# Connectors.net
KiCad netlist of a schematic drawn in Altium Designer
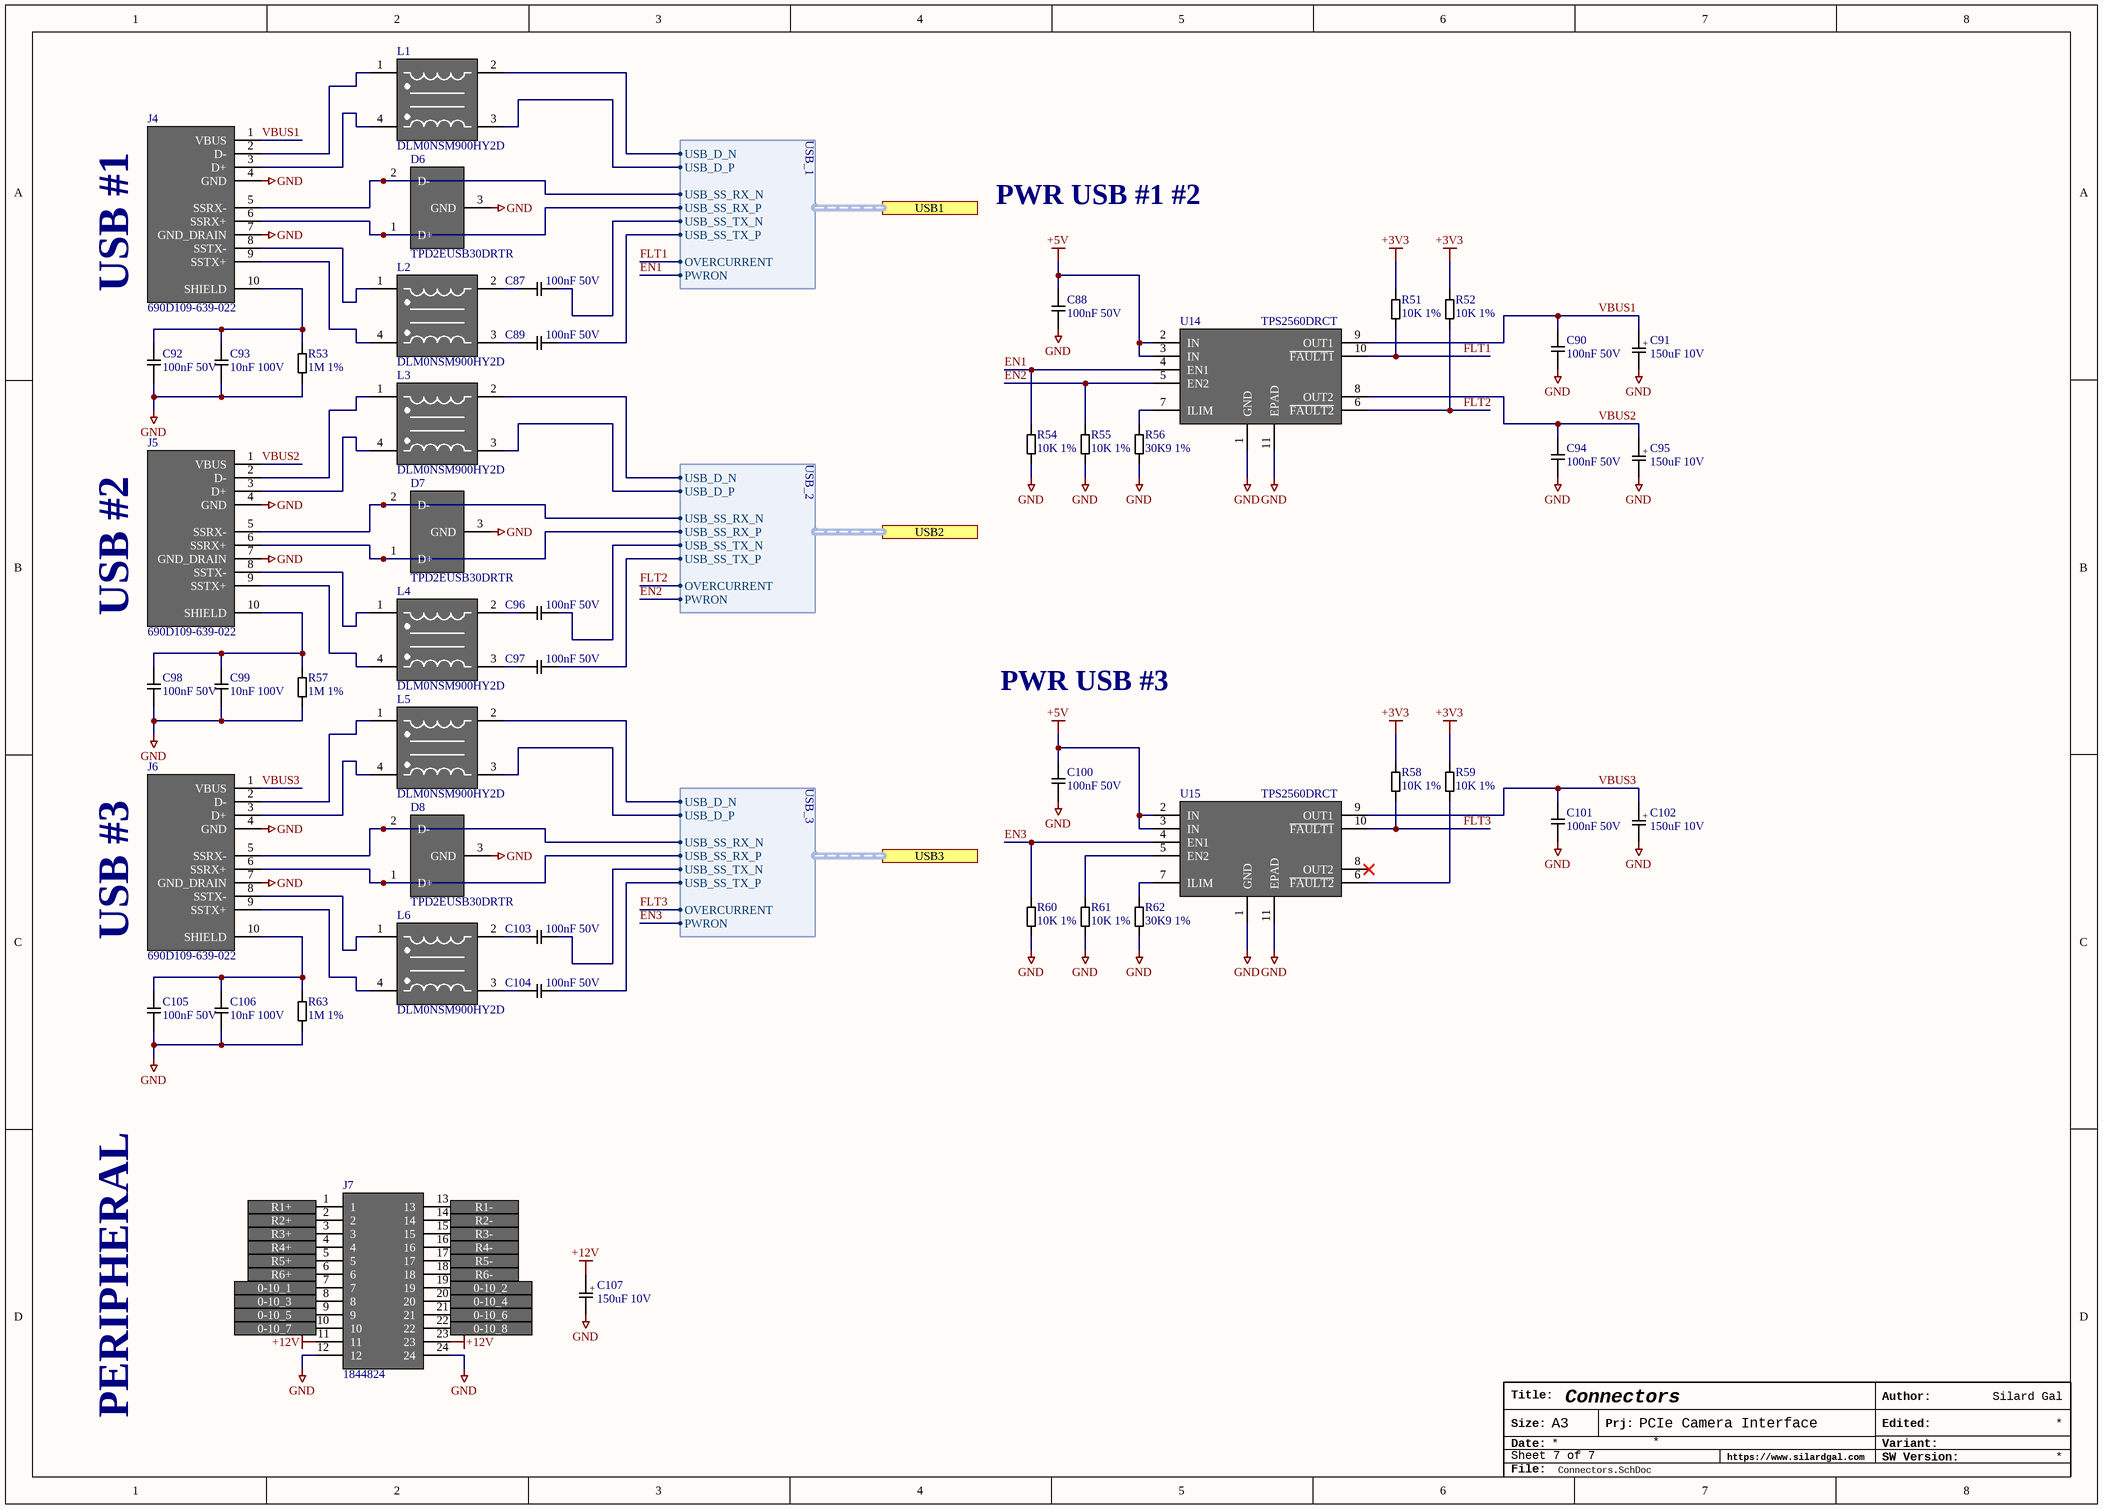
[diagram p0: Connectors.SchDoc]

(export (version "E")
  (design (tool "Eeschema 10.0.6"))
  (components
    (comp (ref "C87")
      (value "100nF 50V")
      (footprint "CAPC1005X06N")
      (description "0.1 µF ±10% 16V Ceramic Capacitor X7R 0402 (1005 Metric)")
      (fields (field (name "MPN") "GRM155R71C104KA88J"))
      (libsource (lib "PCIe_Camera_Interface_Library") (part "100nF 50V_1"))
    )
    (comp (ref "C88")
      (value "100nF 50V")
      (footprint "CAPC1608X06N")
      (description "0.1 µF ±10% 50V Ceramic Capacitor X7R 0603 (1608 Metric)")
      (fields (field (name "MPN") "GCM188R71H104KA57D"))
      (libsource (lib "PCIe_Camera_Interface_Library") (part "100nF 50V"))
    )
    (comp (ref "C89")
      (value "100nF 50V")
      (footprint "CAPC1005X06N")
      (description "0.1 µF ±10% 16V Ceramic Capacitor X7R 0402 (1005 Metric)")
      (fields (field (name "MPN") "GRM155R71C104KA88J"))
      (libsource (lib "PCIe_Camera_Interface_Library") (part "100nF 50V_1"))
    )
    (comp (ref "C90")
      (value "100nF 50V")
      (footprint "CAPC1608X06N")
      (description "0.1 µF ±10% 50V Ceramic Capacitor X7R 0603 (1608 Metric)")
      (fields (field (name "MPN") "GCM188R71H104KA57D"))
      (libsource (lib "PCIe_Camera_Interface_Library") (part "100nF 50V"))
    )
    (comp (ref "C91")
      (value "150uF 10V")
      (footprint "CAP66x66x58")
      (description "150 µF 10 V Aluminum - Polymer Capacitors Radial, Can - SMD 30mOhm 2000 Hrs @ 105°C")
      (fields (field (name "MPN") "875105244011"))
      (libsource (lib "PCIe_Camera_Interface_Library") (part "150uF 10V"))
    )
    (comp (ref "C92")
      (value "100nF 50V")
      (footprint "CAPC1608X06N")
      (description "0.1 µF ±10% 50V Ceramic Capacitor X7R 0603 (1608 Metric)")
      (fields (field (name "MPN") "GCM188R71H104KA57D"))
      (libsource (lib "PCIe_Camera_Interface_Library") (part "100nF 50V"))
    )
    (comp (ref "C93")
      (value "10nF 100V")
      (footprint "CAPC1608X06N")
      (description "10000 pF ±10% 100V Ceramic Capacitor X7R 0603 (1608 Metric)")
      (fields (field (name "MPN") "GCM188R72A103KA37D"))
      (libsource (lib "PCIe_Camera_Interface_Library") (part "10nF 100V"))
    )
    (comp (ref "C94")
      (value "100nF 50V")
      (footprint "CAPC1608X06N")
      (description "0.1 µF ±10% 50V Ceramic Capacitor X7R 0603 (1608 Metric)")
      (fields (field (name "MPN") "GCM188R71H104KA57D"))
      (libsource (lib "PCIe_Camera_Interface_Library") (part "100nF 50V"))
    )
    (comp (ref "C95")
      (value "150uF 10V")
      (footprint "CAP66x66x58")
      (description "150 µF 10 V Aluminum - Polymer Capacitors Radial, Can - SMD 30mOhm 2000 Hrs @ 105°C")
      (fields (field (name "MPN") "875105244011"))
      (libsource (lib "PCIe_Camera_Interface_Library") (part "150uF 10V"))
    )
    (comp (ref "C96")
      (value "100nF 50V")
      (footprint "CAPC1005X06N")
      (description "0.1 µF ±10% 16V Ceramic Capacitor X7R 0402 (1005 Metric)")
      (fields (field (name "MPN") "GRM155R71C104KA88J"))
      (libsource (lib "PCIe_Camera_Interface_Library") (part "100nF 50V_1"))
    )
    (comp (ref "C97")
      (value "100nF 50V")
      (footprint "CAPC1005X06N")
      (description "0.1 µF ±10% 16V Ceramic Capacitor X7R 0402 (1005 Metric)")
      (fields (field (name "MPN") "GRM155R71C104KA88J"))
      (libsource (lib "PCIe_Camera_Interface_Library") (part "100nF 50V_1"))
    )
    (comp (ref "C98")
      (value "100nF 50V")
      (footprint "CAPC1608X06N")
      (description "0.1 µF ±10% 50V Ceramic Capacitor X7R 0603 (1608 Metric)")
      (fields (field (name "MPN") "GCM188R71H104KA57D"))
      (libsource (lib "PCIe_Camera_Interface_Library") (part "100nF 50V"))
    )
    (comp (ref "C99")
      (value "10nF 100V")
      (footprint "CAPC1608X06N")
      (description "10000 pF ±10% 100V Ceramic Capacitor X7R 0603 (1608 Metric)")
      (fields (field (name "MPN") "GCM188R72A103KA37D"))
      (libsource (lib "PCIe_Camera_Interface_Library") (part "10nF 100V"))
    )
    (comp (ref "C100")
      (value "100nF 50V")
      (footprint "CAPC1608X06N")
      (description "0.1 µF ±10% 50V Ceramic Capacitor X7R 0603 (1608 Metric)")
      (fields (field (name "MPN") "GCM188R71H104KA57D"))
      (libsource (lib "PCIe_Camera_Interface_Library") (part "100nF 50V"))
    )
    (comp (ref "C101")
      (value "100nF 50V")
      (footprint "CAPC1608X06N")
      (description "0.1 µF ±10% 50V Ceramic Capacitor X7R 0603 (1608 Metric)")
      (fields (field (name "MPN") "GCM188R71H104KA57D"))
      (libsource (lib "PCIe_Camera_Interface_Library") (part "100nF 50V"))
    )
    (comp (ref "C102")
      (value "150uF 10V")
      (footprint "CAP66x66x58")
      (description "150 µF 10 V Aluminum - Polymer Capacitors Radial, Can - SMD 30mOhm 2000 Hrs @ 105°C")
      (fields (field (name "MPN") "875105244011"))
      (libsource (lib "PCIe_Camera_Interface_Library") (part "150uF 10V"))
    )
    (comp (ref "C103")
      (value "100nF 50V")
      (footprint "CAPC1005X06N")
      (description "0.1 µF ±10% 16V Ceramic Capacitor X7R 0402 (1005 Metric)")
      (fields (field (name "MPN") "GRM155R71C104KA88J"))
      (libsource (lib "PCIe_Camera_Interface_Library") (part "100nF 50V_1"))
    )
    (comp (ref "C104")
      (value "100nF 50V")
      (footprint "CAPC1005X06N")
      (description "0.1 µF ±10% 16V Ceramic Capacitor X7R 0402 (1005 Metric)")
      (fields (field (name "MPN") "GRM155R71C104KA88J"))
      (libsource (lib "PCIe_Camera_Interface_Library") (part "100nF 50V_1"))
    )
    (comp (ref "C105")
      (value "100nF 50V")
      (footprint "CAPC1608X06N")
      (description "0.1 µF ±10% 50V Ceramic Capacitor X7R 0603 (1608 Metric)")
      (fields (field (name "MPN") "GCM188R71H104KA57D"))
      (libsource (lib "PCIe_Camera_Interface_Library") (part "100nF 50V"))
    )
    (comp (ref "C106")
      (value "10nF 100V")
      (footprint "CAPC1608X06N")
      (description "10000 pF ±10% 100V Ceramic Capacitor X7R 0603 (1608 Metric)")
      (fields (field (name "MPN") "GCM188R72A103KA37D"))
      (libsource (lib "PCIe_Camera_Interface_Library") (part "10nF 100V"))
    )
    (comp (ref "C107")
      (value "150uF 10V")
      (footprint "CAP66x66x58")
      (description "150 µF 10 V Aluminum - Polymer Capacitors Radial, Can - SMD 30mOhm 2000 Hrs @ 105°C")
      (fields (field (name "MPN") "875105244011"))
      (libsource (lib "PCIe_Camera_Interface_Library") (part "150uF 10V"))
    )
    (comp (ref "D6")
      (value "TPD2EUSB30DRTR")
      (footprint "SOTFL35P100X50-3N")
      (description "8V Clamp 5A (8/20µs) Ipp Tvs Diode Surface Mount SOT-3")
      (libsource (lib "PCIe_Camera_Interface_Library") (part "TPD2EUSB30DRTR"))
    )
    (comp (ref "D7")
      (value "TPD2EUSB30DRTR")
      (footprint "SOTFL35P100X50-3N")
      (description "8V Clamp 5A (8/20µs) Ipp Tvs Diode Surface Mount SOT-3")
      (libsource (lib "PCIe_Camera_Interface_Library") (part "TPD2EUSB30DRTR"))
    )
    (comp (ref "D8")
      (value "TPD2EUSB30DRTR")
      (footprint "SOTFL35P100X50-3N")
      (description "8V Clamp 5A (8/20µs) Ipp Tvs Diode Surface Mount SOT-3")
      (libsource (lib "PCIe_Camera_Interface_Library") (part "TPD2EUSB30DRTR"))
    )
    (comp (ref "J4")
      (value "690D109-639-022")
      (footprint "690D109-639-022")
      (description "USB-A (USB TYPE-A) USB 3.0 Receptacle Connector 9 Position Through Hole, Right Angle")
      (libsource (lib "PCIe_Camera_Interface_Library") (part "690D109-639-022"))
    )
    (comp (ref "J5")
      (value "690D109-639-022")
      (footprint "690D109-639-022")
      (description "USB-A (USB TYPE-A) USB 3.0 Receptacle Connector 9 Position Through Hole, Right Angle")
      (libsource (lib "PCIe_Camera_Interface_Library") (part "690D109-639-022"))
    )
    (comp (ref "J6")
      (value "690D109-639-022")
      (footprint "690D109-639-022")
      (description "USB-A (USB TYPE-A) USB 3.0 Receptacle Connector 9 Position Through Hole, Right Angle")
      (libsource (lib "PCIe_Camera_Interface_Library") (part "690D109-639-022"))
    )
    (comp (ref "J7")
      (value "1844824")
      (footprint "PHOENIX_1844824")
      (libsource (lib "PCIe_Camera_Interface_Library") (part "1844824"))
    )
    (comp (ref "L1")
      (value "DLM0NSM900HY2D")
      (footprint "DLM0NSM900HY2D")
      (description "2 Line Common Mode Choke Surface Mount 90 Ohms @ 100 MHz 100mA DCR 4Ohm")
      (libsource (lib "PCIe_Camera_Interface_Library") (part "DLM0NSM900HY2D"))
    )
    (comp (ref "L2")
      (value "DLM0NSM900HY2D")
      (footprint "DLM0NSM900HY2D")
      (description "2 Line Common Mode Choke Surface Mount 90 Ohms @ 100 MHz 100mA DCR 4Ohm")
      (libsource (lib "PCIe_Camera_Interface_Library") (part "DLM0NSM900HY2D"))
    )
    (comp (ref "L3")
      (value "DLM0NSM900HY2D")
      (footprint "DLM0NSM900HY2D")
      (description "2 Line Common Mode Choke Surface Mount 90 Ohms @ 100 MHz 100mA DCR 4Ohm")
      (libsource (lib "PCIe_Camera_Interface_Library") (part "DLM0NSM900HY2D"))
    )
    (comp (ref "L4")
      (value "DLM0NSM900HY2D")
      (footprint "DLM0NSM900HY2D")
      (description "2 Line Common Mode Choke Surface Mount 90 Ohms @ 100 MHz 100mA DCR 4Ohm")
      (libsource (lib "PCIe_Camera_Interface_Library") (part "DLM0NSM900HY2D"))
    )
    (comp (ref "L5")
      (value "DLM0NSM900HY2D")
      (footprint "DLM0NSM900HY2D")
      (description "2 Line Common Mode Choke Surface Mount 90 Ohms @ 100 MHz 100mA DCR 4Ohm")
      (libsource (lib "PCIe_Camera_Interface_Library") (part "DLM0NSM900HY2D"))
    )
    (comp (ref "L6")
      (value "DLM0NSM900HY2D")
      (footprint "DLM0NSM900HY2D")
      (description "2 Line Common Mode Choke Surface Mount 90 Ohms @ 100 MHz 100mA DCR 4Ohm")
      (libsource (lib "PCIe_Camera_Interface_Library") (part "DLM0NSM900HY2D"))
    )
    (comp (ref "R51")
      (value "10K 1%")
      (footprint "RESC1608X06N")
      (description "10 kOhms ±1% 0.1W, 1/10W Chip Resistor 0603 (1608 Metric) Automotive AEC-Q200 Thick Film")
      (fields (field (name "MPN") "ERJ-3EKF1002V"))
      (libsource (lib "PCIe_Camera_Interface_Library") (part "10K 1%"))
    )
    (comp (ref "R52")
      (value "10K 1%")
      (footprint "RESC1608X06N")
      (description "10 kOhms ±1% 0.1W, 1/10W Chip Resistor 0603 (1608 Metric) Automotive AEC-Q200 Thick Film")
      (fields (field (name "MPN") "ERJ-3EKF1002V"))
      (libsource (lib "PCIe_Camera_Interface_Library") (part "10K 1%"))
    )
    (comp (ref "R53")
      (value "1M 1%")
      (footprint "RESC1608X06N")
      (description "RES SMD 1M OHM 1% 1/10W 0603")
      (fields (field (name "MPN") "ERJ-3EKF1004V"))
      (libsource (lib "PCIe_Camera_Interface_Library") (part "1M 1%"))
    )
    (comp (ref "R54")
      (value "10K 1%")
      (footprint "RESC1608X06N")
      (description "10 kOhms ±1% 0.1W, 1/10W Chip Resistor 0603 (1608 Metric) Automotive AEC-Q200 Thick Film")
      (fields (field (name "MPN") "ERJ-3EKF1002V"))
      (libsource (lib "PCIe_Camera_Interface_Library") (part "10K 1%"))
    )
    (comp (ref "R55")
      (value "10K 1%")
      (footprint "RESC1608X06N")
      (description "10 kOhms ±1% 0.1W, 1/10W Chip Resistor 0603 (1608 Metric) Automotive AEC-Q200 Thick Film")
      (fields (field (name "MPN") "ERJ-3EKF1002V"))
      (libsource (lib "PCIe_Camera_Interface_Library") (part "10K 1%"))
    )
    (comp (ref "R56")
      (value "30K9 1%")
      (footprint "RESC1608X06N")
      (description "30.9 kOhms ±1% 0.1W, 1/10W Chip Resistor 0603 (1608 Metric) Automotive AEC-Q200 Thick Film")
      (fields (field (name "MPN") "ERJ-3EKF3092V"))
      (libsource (lib "PCIe_Camera_Interface_Library") (part "30K9 1%"))
    )
    (comp (ref "R57")
      (value "1M 1%")
      (footprint "RESC1608X06N")
      (description "RES SMD 1M OHM 1% 1/10W 0603")
      (fields (field (name "MPN") "ERJ-3EKF1004V"))
      (libsource (lib "PCIe_Camera_Interface_Library") (part "1M 1%"))
    )
    (comp (ref "R58")
      (value "10K 1%")
      (footprint "RESC1608X06N")
      (description "10 kOhms ±1% 0.1W, 1/10W Chip Resistor 0603 (1608 Metric) Automotive AEC-Q200 Thick Film")
      (fields (field (name "MPN") "ERJ-3EKF1002V"))
      (libsource (lib "PCIe_Camera_Interface_Library") (part "10K 1%"))
    )
    (comp (ref "R59")
      (value "10K 1%")
      (footprint "RESC1608X06N")
      (description "10 kOhms ±1% 0.1W, 1/10W Chip Resistor 0603 (1608 Metric) Automotive AEC-Q200 Thick Film")
      (fields (field (name "MPN") "ERJ-3EKF1002V"))
      (libsource (lib "PCIe_Camera_Interface_Library") (part "10K 1%"))
    )
    (comp (ref "R60")
      (value "10K 1%")
      (footprint "RESC1608X06N")
      (description "10 kOhms ±1% 0.1W, 1/10W Chip Resistor 0603 (1608 Metric) Automotive AEC-Q200 Thick Film")
      (fields (field (name "MPN") "ERJ-3EKF1002V"))
      (libsource (lib "PCIe_Camera_Interface_Library") (part "10K 1%"))
    )
    (comp (ref "R61")
      (value "10K 1%")
      (footprint "RESC1608X06N")
      (description "10 kOhms ±1% 0.1W, 1/10W Chip Resistor 0603 (1608 Metric) Automotive AEC-Q200 Thick Film")
      (fields (field (name "MPN") "ERJ-3EKF1002V"))
      (libsource (lib "PCIe_Camera_Interface_Library") (part "10K 1%"))
    )
    (comp (ref "R62")
      (value "30K9 1%")
      (footprint "RESC1608X06N")
      (description "30.9 kOhms ±1% 0.1W, 1/10W Chip Resistor 0603 (1608 Metric) Automotive AEC-Q200 Thick Film")
      (fields (field (name "MPN") "ERJ-3EKF3092V"))
      (libsource (lib "PCIe_Camera_Interface_Library") (part "30K9 1%"))
    )
    (comp (ref "R63")
      (value "1M 1%")
      (footprint "RESC1608X06N")
      (description "RES SMD 1M OHM 1% 1/10W 0603")
      (fields (field (name "MPN") "ERJ-3EKF1004V"))
      (libsource (lib "PCIe_Camera_Interface_Library") (part "1M 1%"))
    )
    (comp (ref "U14")
      (value "TPS2560DRCT")
      (footprint "10VSON")
      (description "Power Switch/Driver 1:2 N-Channel 2.5A 10-VSON (3x3)")
      (libsource (lib "PCIe_Camera_Interface_Library") (part "TPS2560DRCT"))
    )
    (comp (ref "U15")
      (value "TPS2560DRCT")
      (footprint "10VSON")
      (description "Power Switch/Driver 1:2 N-Channel 2.5A 10-VSON (3x3)")
      (libsource (lib "PCIe_Camera_Interface_Library") (part "TPS2560DRCT"))
    )
  )
  (nets
    (net (code "4") (name "+3V3") (class "Default")
      (node (ref "R51") (pin "2") (pinfunction "2_2") (pintype "passive"))
      (node (ref "R52") (pin "2") (pinfunction "2_2") (pintype "passive"))
      (node (ref "R58") (pin "2") (pinfunction "2_2") (pintype "passive"))
      (node (ref "R59") (pin "2") (pinfunction "2_2") (pintype "passive"))
    )
    (net (code "5") (name "+5V") (class "Default")
      (node (ref "C100") (pin "2") (pinfunction "2_2") (pintype "passive"))
      (node (ref "C88") (pin "2") (pinfunction "2_2") (pintype "passive"))
      (node (ref "U14") (pin "2") (pinfunction "IN_2") (pintype "passive"))
      (node (ref "U14") (pin "3") (pinfunction "IN_3") (pintype "passive"))
      (node (ref "U15") (pin "2") (pinfunction "IN_2") (pintype "passive"))
      (node (ref "U15") (pin "3") (pinfunction "IN_3") (pintype "passive"))
    )
    (net (code "6") (name "+12V") (class "Default")
      (node (ref "C107") (pin "1") (pinfunction "1_1") (pintype "passive"))
      (node (ref "J7") (pin "11") (pinfunction "11_11") (pintype "passive"))
      (node (ref "J7") (pin "23") (pinfunction "23_23") (pintype "passive"))
    )
    (net (code "7") (name "/0-10_1") (class "Default")
      (node (ref "J7") (pin "7") (pinfunction "7_7") (pintype "passive"))
    )
    (net (code "8") (name "/0-10_2") (class "Default")
      (node (ref "J7") (pin "19") (pinfunction "19_19") (pintype "passive"))
    )
    (net (code "9") (name "/0-10_3") (class "Default")
      (node (ref "J7") (pin "8") (pinfunction "8_8") (pintype "passive"))
    )
    (net (code "10") (name "/0-10_4") (class "Default")
      (node (ref "J7") (pin "20") (pinfunction "20_20") (pintype "passive"))
    )
    (net (code "11") (name "/0-10_5") (class "Default")
      (node (ref "J7") (pin "9") (pinfunction "9_9") (pintype "passive"))
    )
    (net (code "12") (name "/0-10_6") (class "Default")
      (node (ref "J7") (pin "21") (pinfunction "21_21") (pintype "passive"))
    )
    (net (code "13") (name "/0-10_7") (class "Default")
      (node (ref "J7") (pin "10") (pinfunction "10_10") (pintype "passive"))
    )
    (net (code "14") (name "/0-10_8") (class "Default")
      (node (ref "J7") (pin "22") (pinfunction "22_22") (pintype "passive"))
    )
    (net (code "15") (name "/EN1") (class "Default")
      (node (ref "R54") (pin "2") (pinfunction "2_2") (pintype "passive"))
      (node (ref "U14") (pin "4") (pinfunction "EN1_4") (pintype "passive"))
    )
    (net (code "16") (name "/EN2") (class "Default")
      (node (ref "R55") (pin "2") (pinfunction "2_2") (pintype "passive"))
      (node (ref "U14") (pin "5") (pinfunction "EN2_5") (pintype "passive"))
    )
    (net (code "17") (name "/EN3") (class "Default")
      (node (ref "R60") (pin "2") (pinfunction "2_2") (pintype "passive"))
      (node (ref "U15") (pin "4") (pinfunction "EN1_4") (pintype "passive"))
    )
    (net (code "18") (name "/FLT1") (class "Default")
      (node (ref "R51") (pin "1") (pinfunction "1_1") (pintype "passive"))
      (node (ref "U14") (pin "10") (pinfunction "~{FAULT1}_10") (pintype "passive"))
    )
    (net (code "19") (name "/FLT2") (class "Default")
      (node (ref "R52") (pin "1") (pinfunction "1_1") (pintype "passive"))
      (node (ref "U14") (pin "6") (pinfunction "~{FAULT2}_6") (pintype "passive"))
    )
    (net (code "20") (name "/FLT3") (class "Default")
      (node (ref "R58") (pin "1") (pinfunction "1_1") (pintype "passive"))
      (node (ref "U15") (pin "10") (pinfunction "~{FAULT1}_10") (pintype "passive"))
    )
    (net (code "21") (name "/R1+") (class "Default")
      (node (ref "J7") (pin "1") (pinfunction "1_1") (pintype "passive"))
    )
    (net (code "22") (name "/R1-") (class "Default")
      (node (ref "J7") (pin "13") (pinfunction "13_13") (pintype "passive"))
    )
    (net (code "23") (name "/R2+") (class "Default")
      (node (ref "J7") (pin "2") (pinfunction "2_2") (pintype "passive"))
    )
    (net (code "24") (name "/R2-") (class "Default")
      (node (ref "J7") (pin "14") (pinfunction "14_14") (pintype "passive"))
    )
    (net (code "25") (name "/R3+") (class "Default")
      (node (ref "J7") (pin "3") (pinfunction "3_3") (pintype "passive"))
    )
    (net (code "26") (name "/R3-") (class "Default")
      (node (ref "J7") (pin "15") (pinfunction "15_15") (pintype "passive"))
    )
    (net (code "27") (name "/R4+") (class "Default")
      (node (ref "J7") (pin "4") (pinfunction "4_4") (pintype "passive"))
    )
    (net (code "28") (name "/R4-") (class "Default")
      (node (ref "J7") (pin "16") (pinfunction "16_16") (pintype "passive"))
    )
    (net (code "29") (name "/R5+") (class "Default")
      (node (ref "J7") (pin "5") (pinfunction "5_5") (pintype "passive"))
    )
    (net (code "30") (name "/R5-") (class "Default")
      (node (ref "J7") (pin "17") (pinfunction "17_17") (pintype "passive"))
    )
    (net (code "31") (name "/R6+") (class "Default")
      (node (ref "J7") (pin "6") (pinfunction "6_6") (pintype "passive"))
    )
    (net (code "32") (name "/R6-") (class "Default")
      (node (ref "J7") (pin "18") (pinfunction "18_18") (pintype "passive"))
    )
    (net (code "33") (name "/VBUS1") (class "Default")
      (node (ref "C90") (pin "2") (pinfunction "2_2") (pintype "passive"))
      (node (ref "C91") (pin "1") (pinfunction "1_1") (pintype "passive"))
      (node (ref "J4") (pin "1") (pinfunction "VBUS_1") (pintype "passive"))
      (node (ref "U14") (pin "9") (pinfunction "OUT1_9") (pintype "passive"))
    )
    (net (code "34") (name "/VBUS2") (class "Default")
      (node (ref "C94") (pin "2") (pinfunction "2_2") (pintype "passive"))
      (node (ref "C95") (pin "1") (pinfunction "1_1") (pintype "passive"))
      (node (ref "J5") (pin "1") (pinfunction "VBUS_1") (pintype "passive"))
      (node (ref "U14") (pin "8") (pinfunction "OUT2_8") (pintype "passive"))
    )
    (net (code "35") (name "/VBUS3") (class "Default")
      (node (ref "C101") (pin "2") (pinfunction "2_2") (pintype "passive"))
      (node (ref "C102") (pin "1") (pinfunction "1_1") (pintype "passive"))
      (node (ref "J6") (pin "1") (pinfunction "VBUS_1") (pintype "passive"))
      (node (ref "U15") (pin "9") (pinfunction "OUT1_9") (pintype "passive"))
    )
    (net (code "39") (name "GND") (class "Default")
      (node (ref "C100") (pin "1") (pinfunction "1_1") (pintype "passive"))
      (node (ref "C101") (pin "1") (pinfunction "1_1") (pintype "passive"))
      (node (ref "C102") (pin "2") (pinfunction "2_2") (pintype "passive"))
      (node (ref "C105") (pin "1") (pinfunction "1_1") (pintype "passive"))
      (node (ref "C106") (pin "1") (pinfunction "1_1") (pintype "passive"))
      (node (ref "C107") (pin "2") (pinfunction "2_2") (pintype "passive"))
      (node (ref "C88") (pin "1") (pinfunction "1_1") (pintype "passive"))
      (node (ref "C90") (pin "1") (pinfunction "1_1") (pintype "passive"))
      (node (ref "C91") (pin "2") (pinfunction "2_2") (pintype "passive"))
      (node (ref "C92") (pin "1") (pinfunction "1_1") (pintype "passive"))
      (node (ref "C93") (pin "1") (pinfunction "1_1") (pintype "passive"))
      (node (ref "C94") (pin "1") (pinfunction "1_1") (pintype "passive"))
      (node (ref "C95") (pin "2") (pinfunction "2_2") (pintype "passive"))
      (node (ref "C98") (pin "1") (pinfunction "1_1") (pintype "passive"))
      (node (ref "C99") (pin "1") (pinfunction "1_1") (pintype "passive"))
      (node (ref "D6") (pin "3") (pinfunction "GND_3") (pintype "passive"))
      (node (ref "D7") (pin "3") (pinfunction "GND_3") (pintype "passive"))
      (node (ref "D8") (pin "3") (pinfunction "GND_3") (pintype "passive"))
      (node (ref "J4") (pin "4") (pinfunction "GND_4") (pintype "passive"))
      (node (ref "J4") (pin "7") (pinfunction "GND_DRAIN_7") (pintype "passive"))
      (node (ref "J5") (pin "4") (pinfunction "GND_4") (pintype "passive"))
      (node (ref "J5") (pin "7") (pinfunction "GND_DRAIN_7") (pintype "passive"))
      (node (ref "J6") (pin "4") (pinfunction "GND_4") (pintype "passive"))
      (node (ref "J6") (pin "7") (pinfunction "GND_DRAIN_7") (pintype "passive"))
      (node (ref "J7") (pin "12") (pinfunction "12_12") (pintype "passive"))
      (node (ref "J7") (pin "24") (pinfunction "24_24") (pintype "passive"))
      (node (ref "R53") (pin "1") (pinfunction "1_1") (pintype "passive"))
      (node (ref "R54") (pin "1") (pinfunction "1_1") (pintype "passive"))
      (node (ref "R55") (pin "1") (pinfunction "1_1") (pintype "passive"))
      (node (ref "R56") (pin "1") (pinfunction "1_1") (pintype "passive"))
      (node (ref "R57") (pin "1") (pinfunction "1_1") (pintype "passive"))
      (node (ref "R60") (pin "1") (pinfunction "1_1") (pintype "passive"))
      (node (ref "R61") (pin "1") (pinfunction "1_1") (pintype "passive"))
      (node (ref "R62") (pin "1") (pinfunction "1_1") (pintype "passive"))
      (node (ref "R63") (pin "1") (pinfunction "1_1") (pintype "passive"))
      (node (ref "U14") (pin "1") (pinfunction "GND_1") (pintype "passive"))
      (node (ref "U14") (pin "11") (pinfunction "EPAD_11") (pintype "passive"))
      (node (ref "U15") (pin "1") (pinfunction "GND_1") (pintype "passive"))
      (node (ref "U15") (pin "11") (pinfunction "EPAD_11") (pintype "passive"))
    )
    (net (code "40") (name "Net-(C87-Pad1)") (class "Default")
      (node (ref "C87") (pin "1") (pinfunction "1_1") (pintype "passive"))
      (node (ref "L2") (pin "2") (pinfunction "2_2") (pintype "passive"))
    )
    (net (code "41") (name "Net-(C89-Pad1)") (class "Default")
      (node (ref "C89") (pin "1") (pinfunction "1_1") (pintype "passive"))
      (node (ref "L2") (pin "3") (pinfunction "3_3") (pintype "passive"))
    )
    (net (code "42") (name "Net-(C96-Pad1)") (class "Default")
      (node (ref "C96") (pin "1") (pinfunction "1_1") (pintype "passive"))
      (node (ref "L4") (pin "2") (pinfunction "2_2") (pintype "passive"))
    )
    (net (code "43") (name "Net-(C97-Pad1)") (class "Default")
      (node (ref "C97") (pin "1") (pinfunction "1_1") (pintype "passive"))
      (node (ref "L4") (pin "3") (pinfunction "3_3") (pintype "passive"))
    )
    (net (code "44") (name "Net-(C103-Pad1)") (class "Default")
      (node (ref "C103") (pin "1") (pinfunction "1_1") (pintype "passive"))
      (node (ref "L6") (pin "2") (pinfunction "2_2") (pintype "passive"))
    )
    (net (code "45") (name "Net-(C104-Pad1)") (class "Default")
      (node (ref "C104") (pin "1") (pinfunction "1_1") (pintype "passive"))
      (node (ref "L6") (pin "3") (pinfunction "3_3") (pintype "passive"))
    )
    (net (code "46") (name "Net-(D6-D+)") (class "Default")
      (node (ref "D6") (pin "1") (pinfunction "D+_1") (pintype "passive"))
      (node (ref "J4") (pin "6") (pinfunction "SSRX+_6") (pintype "passive"))
    )
    (net (code "47") (name "Net-(D6-D-)") (class "Default")
      (node (ref "D6") (pin "2") (pinfunction "D-_2") (pintype "passive"))
      (node (ref "J4") (pin "5") (pinfunction "SSRX-_5") (pintype "passive"))
    )
    (net (code "48") (name "Net-(D7-D+)") (class "Default")
      (node (ref "D7") (pin "1") (pinfunction "D+_1") (pintype "passive"))
      (node (ref "J5") (pin "6") (pinfunction "SSRX+_6") (pintype "passive"))
    )
    (net (code "49") (name "Net-(D7-D-)") (class "Default")
      (node (ref "D7") (pin "2") (pinfunction "D-_2") (pintype "passive"))
      (node (ref "J5") (pin "5") (pinfunction "SSRX-_5") (pintype "passive"))
    )
    (net (code "50") (name "Net-(D8-D+)") (class "Default")
      (node (ref "D8") (pin "1") (pinfunction "D+_1") (pintype "passive"))
      (node (ref "J6") (pin "6") (pinfunction "SSRX+_6") (pintype "passive"))
    )
    (net (code "51") (name "Net-(D8-D-)") (class "Default")
      (node (ref "D8") (pin "2") (pinfunction "D-_2") (pintype "passive"))
      (node (ref "J6") (pin "5") (pinfunction "SSRX-_5") (pintype "passive"))
    )
    (net (code "52") (name "Net-(J4-D+)") (class "Default")
      (node (ref "J4") (pin "3") (pinfunction "D+_3") (pintype "passive"))
      (node (ref "L1") (pin "4") (pinfunction "4_4") (pintype "passive"))
    )
    (net (code "53") (name "Net-(J4-D-)") (class "Default")
      (node (ref "J4") (pin "2") (pinfunction "D-_2") (pintype "passive"))
      (node (ref "L1") (pin "1") (pinfunction "1_1") (pintype "passive"))
    )
    (net (code "54") (name "Net-(J4-SHIELD)") (class "Default")
      (node (ref "C92") (pin "2") (pinfunction "2_2") (pintype "passive"))
      (node (ref "C93") (pin "2") (pinfunction "2_2") (pintype "passive"))
      (node (ref "J4") (pin "10") (pinfunction "SHIELD_10") (pintype "passive"))
      (node (ref "R53") (pin "2") (pinfunction "2_2") (pintype "passive"))
    )
    (net (code "55") (name "Net-(J4-SSTX+)") (class "Default")
      (node (ref "J4") (pin "9") (pinfunction "SSTX+_9") (pintype "passive"))
      (node (ref "L2") (pin "4") (pinfunction "4_4") (pintype "passive"))
    )
    (net (code "56") (name "Net-(J4-SSTX-)") (class "Default")
      (node (ref "J4") (pin "8") (pinfunction "SSTX-_8") (pintype "passive"))
      (node (ref "L2") (pin "1") (pinfunction "1_1") (pintype "passive"))
    )
    (net (code "57") (name "Net-(J5-D+)") (class "Default")
      (node (ref "J5") (pin "3") (pinfunction "D+_3") (pintype "passive"))
      (node (ref "L3") (pin "4") (pinfunction "4_4") (pintype "passive"))
    )
    (net (code "58") (name "Net-(J5-D-)") (class "Default")
      (node (ref "J5") (pin "2") (pinfunction "D-_2") (pintype "passive"))
      (node (ref "L3") (pin "1") (pinfunction "1_1") (pintype "passive"))
    )
    (net (code "59") (name "Net-(J5-SHIELD)") (class "Default")
      (node (ref "C98") (pin "2") (pinfunction "2_2") (pintype "passive"))
      (node (ref "C99") (pin "2") (pinfunction "2_2") (pintype "passive"))
      (node (ref "J5") (pin "10") (pinfunction "SHIELD_10") (pintype "passive"))
      (node (ref "R57") (pin "2") (pinfunction "2_2") (pintype "passive"))
    )
    (net (code "60") (name "Net-(J5-SSTX+)") (class "Default")
      (node (ref "J5") (pin "9") (pinfunction "SSTX+_9") (pintype "passive"))
      (node (ref "L4") (pin "4") (pinfunction "4_4") (pintype "passive"))
    )
    (net (code "61") (name "Net-(J5-SSTX-)") (class "Default")
      (node (ref "J5") (pin "8") (pinfunction "SSTX-_8") (pintype "passive"))
      (node (ref "L4") (pin "1") (pinfunction "1_1") (pintype "passive"))
    )
    (net (code "62") (name "Net-(J6-D+)") (class "Default")
      (node (ref "J6") (pin "3") (pinfunction "D+_3") (pintype "passive"))
      (node (ref "L5") (pin "4") (pinfunction "4_4") (pintype "passive"))
    )
    (net (code "63") (name "Net-(J6-D-)") (class "Default")
      (node (ref "J6") (pin "2") (pinfunction "D-_2") (pintype "passive"))
      (node (ref "L5") (pin "1") (pinfunction "1_1") (pintype "passive"))
    )
    (net (code "64") (name "Net-(J6-SHIELD)") (class "Default")
      (node (ref "C105") (pin "2") (pinfunction "2_2") (pintype "passive"))
      (node (ref "C106") (pin "2") (pinfunction "2_2") (pintype "passive"))
      (node (ref "J6") (pin "10") (pinfunction "SHIELD_10") (pintype "passive"))
      (node (ref "R63") (pin "2") (pinfunction "2_2") (pintype "passive"))
    )
    (net (code "65") (name "Net-(J6-SSTX+)") (class "Default")
      (node (ref "J6") (pin "9") (pinfunction "SSTX+_9") (pintype "passive"))
      (node (ref "L6") (pin "4") (pinfunction "4_4") (pintype "passive"))
    )
    (net (code "66") (name "Net-(J6-SSTX-)") (class "Default")
      (node (ref "J6") (pin "8") (pinfunction "SSTX-_8") (pintype "passive"))
      (node (ref "L6") (pin "1") (pinfunction "1_1") (pintype "passive"))
    )
    (net (code "67") (name "Net-(U14-ILIM)") (class "Default")
      (node (ref "R56") (pin "2") (pinfunction "2_2") (pintype "passive"))
      (node (ref "U14") (pin "7") (pinfunction "ILIM_7") (pintype "passive"))
    )
    (net (code "68") (name "Net-(U15-EN2)") (class "Default")
      (node (ref "R61") (pin "2") (pinfunction "2_2") (pintype "passive"))
      (node (ref "U15") (pin "5") (pinfunction "EN2_5") (pintype "passive"))
    )
    (net (code "69") (name "Net-(U15-ILIM)") (class "Default")
      (node (ref "R62") (pin "2") (pinfunction "2_2") (pintype "passive"))
      (node (ref "U15") (pin "7") (pinfunction "ILIM_7") (pintype "passive"))
    )
    (net (code "70") (name "Net-(U15-~{FAULT2})") (class "Default")
      (node (ref "R59") (pin "1") (pinfunction "1_1") (pintype "passive"))
      (node (ref "U15") (pin "6") (pinfunction "~{FAULT2}_6") (pintype "passive"))
    )
    (net (code "71") (name "unconnected-(C87-Pad2)") (class "Default")
      (node (ref "C87") (pin "2") (pinfunction "2_2") (pintype "passive"))
    )
    (net (code "72") (name "unconnected-(C89-Pad2)") (class "Default")
      (node (ref "C89") (pin "2") (pinfunction "2_2") (pintype "passive"))
    )
    (net (code "73") (name "unconnected-(C96-Pad2)") (class "Default")
      (node (ref "C96") (pin "2") (pinfunction "2_2") (pintype "passive"))
    )
    (net (code "74") (name "unconnected-(C97-Pad2)") (class "Default")
      (node (ref "C97") (pin "2") (pinfunction "2_2") (pintype "passive"))
    )
    (net (code "75") (name "unconnected-(C103-Pad2)") (class "Default")
      (node (ref "C103") (pin "2") (pinfunction "2_2") (pintype "passive"))
    )
    (net (code "76") (name "unconnected-(C104-Pad2)") (class "Default")
      (node (ref "C104") (pin "2") (pinfunction "2_2") (pintype "passive"))
    )
    (net (code "77") (name "unconnected-(L1-Pad2)") (class "Default")
      (node (ref "L1") (pin "2") (pinfunction "2_2") (pintype "passive"))
    )
    (net (code "78") (name "unconnected-(L1-Pad3)") (class "Default")
      (node (ref "L1") (pin "3") (pinfunction "3_3") (pintype "passive"))
    )
    (net (code "79") (name "unconnected-(L3-Pad2)") (class "Default")
      (node (ref "L3") (pin "2") (pinfunction "2_2") (pintype "passive"))
    )
    (net (code "80") (name "unconnected-(L3-Pad3)") (class "Default")
      (node (ref "L3") (pin "3") (pinfunction "3_3") (pintype "passive"))
    )
    (net (code "81") (name "unconnected-(L5-Pad2)") (class "Default")
      (node (ref "L5") (pin "2") (pinfunction "2_2") (pintype "passive"))
    )
    (net (code "82") (name "unconnected-(L5-Pad3)") (class "Default")
      (node (ref "L5") (pin "3") (pinfunction "3_3") (pintype "passive"))
    )
    (net (code "83") (name "unconnected-(U15-OUT2-Pad8)") (class "Default")
      (node (ref "U15") (pin "8") (pinfunction "OUT2_8") (pintype "passive+no_connect"))
    )
  )
)
